# actuators.net
KiCad netlist of a schematic drawn in EAGLE
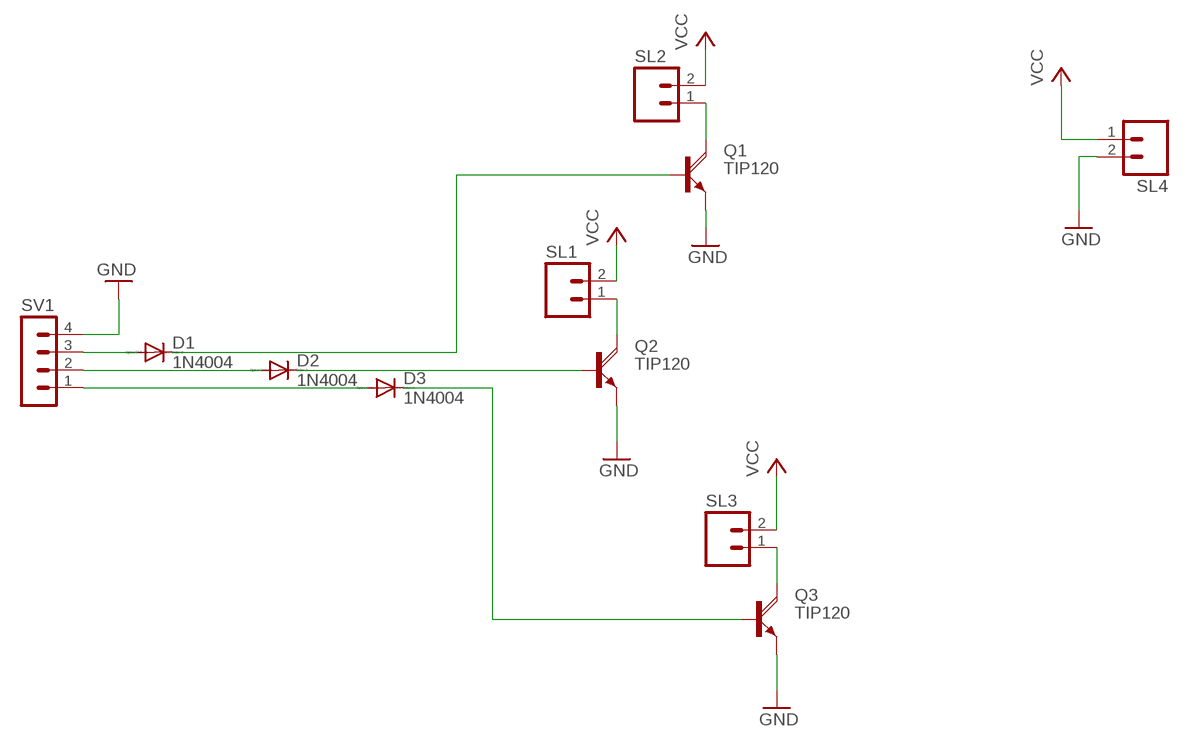
[diagram p0: schematic, sheet 1]

(export (version "E")
  (design (tool "Eeschema 10.0.6"))
  (components
    (comp (ref "D1")
      (value "1N4004")
      (footprint "eagle-import:DO41-10")
      (libsource (lib "eagle-import") (part "1N4004"))
    )
    (comp (ref "D2")
      (value "1N4004")
      (footprint "eagle-import:DO41-10")
      (libsource (lib "eagle-import") (part "1N4004"))
    )
    (comp (ref "D3")
      (value "1N4004")
      (footprint "eagle-import:DO41-10")
      (libsource (lib "eagle-import") (part "1N4004"))
    )
    (comp (ref "Q1")
      (value "TIP120")
      (footprint "eagle-import:TO220AH")
      (libsource (lib "eagle-import") (part "TIP120"))
    )
    (comp (ref "Q2")
      (value "TIP120")
      (footprint "eagle-import:TO220AH")
      (libsource (lib "eagle-import") (part "TIP120"))
    )
    (comp (ref "Q3")
      (value "TIP120")
      (footprint "eagle-import:TO220AH")
      (libsource (lib "eagle-import") (part "TIP120"))
    )
    (comp (ref "SL1")
      (value "MA02")
      (footprint "eagle-import:02PA")
      (libsource (lib "eagle-import") (part "MA02"))
    )
    (comp (ref "SL2")
      (value "MA02")
      (footprint "eagle-import:02PA")
      (libsource (lib "eagle-import") (part "MA02"))
    )
    (comp (ref "SL3")
      (value "MA02")
      (footprint "eagle-import:02PA")
      (libsource (lib "eagle-import") (part "MA02"))
    )
    (comp (ref "SL4")
      (value "MA02")
      (footprint "eagle-import:02PA")
      (libsource (lib "eagle-import") (part "MA02"))
    )
    (comp (ref "SV1")
      (value "MA04-1")
      (footprint "eagle-import:MA04-1")
      (libsource (lib "eagle-import") (part "MA04-1"))
    )
  )
  (nets
    (net (code "1") (name "GND") (class "Default")
      (node (ref "Q1") (pin "E") (pinfunction "E_E") (pintype "passive"))
      (node (ref "Q2") (pin "E") (pinfunction "E_E") (pintype "passive"))
      (node (ref "Q3") (pin "E") (pinfunction "E_E") (pintype "passive"))
      (node (ref "SL4") (pin "2") (pinfunction "2_2") (pintype "passive"))
      (node (ref "SV1") (pin "4") (pinfunction "4_4") (pintype "passive"))
    )
    (net (code "2") (name "Net-(D1-PadA)") (class "Default")
      (node (ref "D1") (pin "A") (pinfunction "A_A") (pintype "passive"))
      (node (ref "SV1") (pin "3") (pinfunction "3_3") (pintype "passive"))
    )
    (net (code "3") (name "Net-(D1-PadC)") (class "Default")
      (node (ref "D1") (pin "C") (pinfunction "C_C") (pintype "passive"))
      (node (ref "Q1") (pin "B") (pinfunction "B_B") (pintype "passive"))
    )
    (net (code "4") (name "Net-(D2-PadA)") (class "Default")
      (node (ref "D2") (pin "A") (pinfunction "A_A") (pintype "passive"))
      (node (ref "SV1") (pin "2") (pinfunction "2_2") (pintype "passive"))
    )
    (net (code "5") (name "Net-(D2-PadC)") (class "Default")
      (node (ref "D2") (pin "C") (pinfunction "C_C") (pintype "passive"))
      (node (ref "Q2") (pin "B") (pinfunction "B_B") (pintype "passive"))
    )
    (net (code "6") (name "Net-(D3-PadA)") (class "Default")
      (node (ref "D3") (pin "A") (pinfunction "A_A") (pintype "passive"))
      (node (ref "SV1") (pin "1") (pinfunction "1_1") (pintype "passive"))
    )
    (net (code "7") (name "Net-(D3-PadC)") (class "Default")
      (node (ref "D3") (pin "C") (pinfunction "C_C") (pintype "passive"))
      (node (ref "Q3") (pin "B") (pinfunction "B_B") (pintype "passive"))
    )
    (net (code "8") (name "Net-(Q1-PadC)") (class "Default")
      (node (ref "Q1") (pin "C") (pinfunction "C_C") (pintype "passive"))
      (node (ref "SL2") (pin "1") (pinfunction "1_1") (pintype "passive"))
    )
    (net (code "9") (name "Net-(Q2-PadC)") (class "Default")
      (node (ref "Q2") (pin "C") (pinfunction "C_C") (pintype "passive"))
      (node (ref "SL1") (pin "1") (pinfunction "1_1") (pintype "passive"))
    )
    (net (code "10") (name "Net-(Q3-PadC)") (class "Default")
      (node (ref "Q3") (pin "C") (pinfunction "C_C") (pintype "passive"))
      (node (ref "SL3") (pin "1") (pinfunction "1_1") (pintype "passive"))
    )
    (net (code "11") (name "VCC") (class "Default")
      (node (ref "SL1") (pin "2") (pinfunction "2_2") (pintype "passive"))
      (node (ref "SL2") (pin "2") (pinfunction "2_2") (pintype "passive"))
      (node (ref "SL3") (pin "2") (pinfunction "2_2") (pintype "passive"))
      (node (ref "SL4") (pin "1") (pinfunction "1_1") (pintype "passive"))
    )
  )
)
